# RS232.net
KiCad netlist of a schematic drawn in Altium Designer
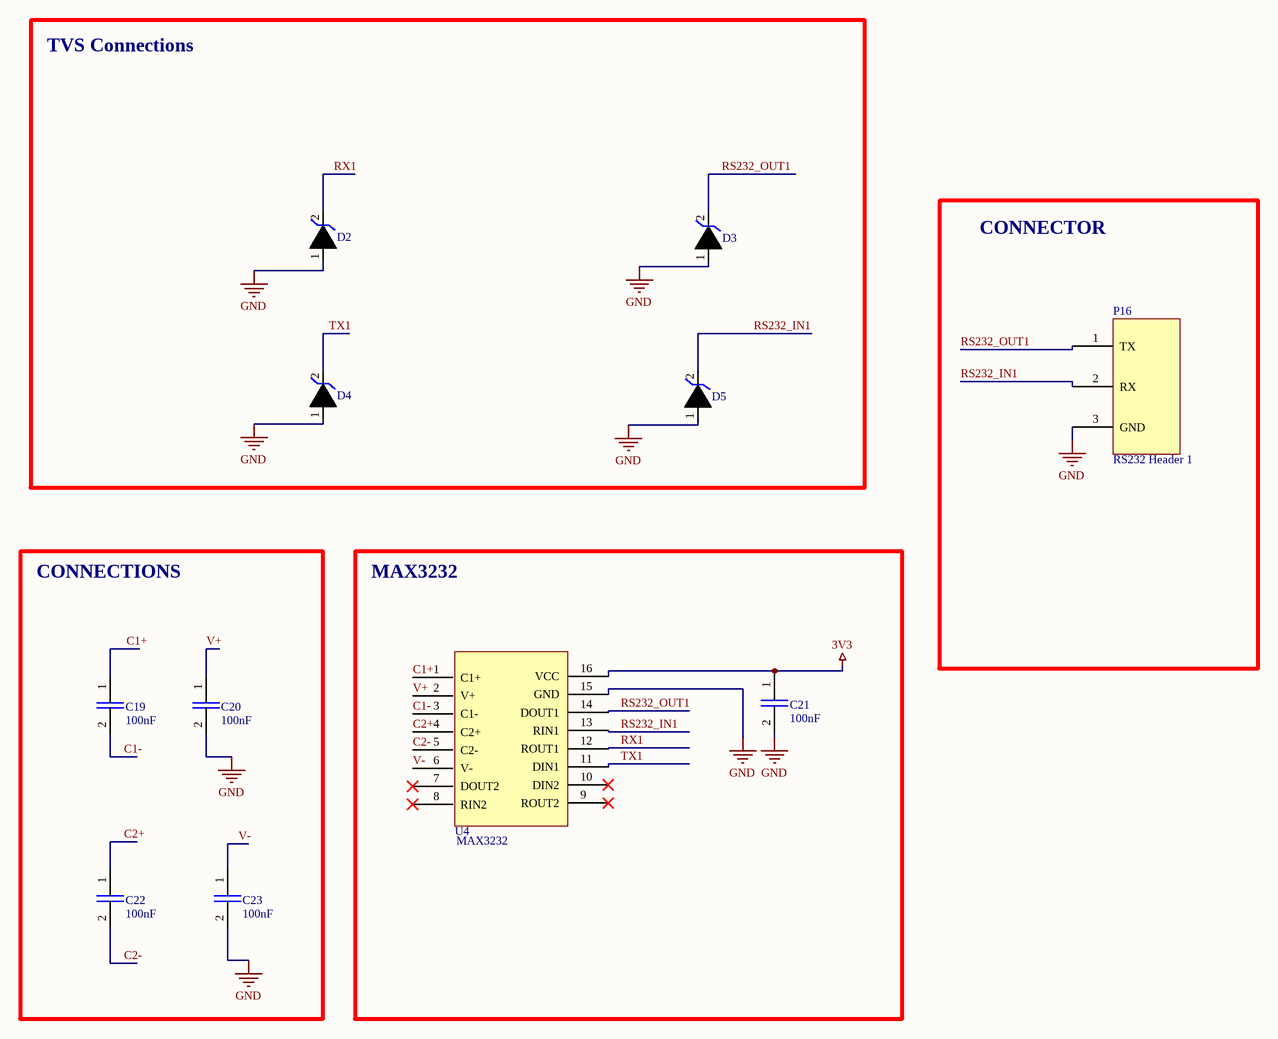
[diagram p0: RS232.SchDoc]

(export (version "E")
  (design (tool "Eeschema 10.0.6"))
  (components
    (comp (ref "C19")
      (value "100nF")
      (footprint "0603 Cap")
      (description "SMD 0603 (ceramic) capacitor")
      (fields
        (field (name "MANUFACTURER") "Murata")
        (field (name "MANUFACTURER PART NUMBER") "GRM21BR71C225KA12L")
      )
      (libsource (lib "Lib") (part "0603 Cap"))
    )
    (comp (ref "C20")
      (value "100nF")
      (footprint "0603 Cap")
      (description "SMD 0603 (ceramic) capacitor")
      (fields
        (field (name "MANUFACTURER") "Murata")
        (field (name "MANUFACTURER PART NUMBER") "GRM21BR71C225KA12L")
      )
      (libsource (lib "Lib") (part "0603 Cap"))
    )
    (comp (ref "C21")
      (value "100nF")
      (footprint "0603 Cap")
      (description "SMD 0603 (ceramic) capacitor")
      (fields
        (field (name "MANUFACTURER") "Murata")
        (field (name "MANUFACTURER PART NUMBER") "GRM21BR71C225KA12L")
      )
      (libsource (lib "Lib") (part "0603 Cap"))
    )
    (comp (ref "C22")
      (value "100nF")
      (footprint "0603 Cap")
      (description "SMD 0603 (ceramic) capacitor")
      (fields
        (field (name "MANUFACTURER") "Murata")
        (field (name "MANUFACTURER PART NUMBER") "GRM21BR71C225KA12L")
      )
      (libsource (lib "Lib") (part "0603 Cap"))
    )
    (comp (ref "C23")
      (value "100nF")
      (footprint "0603 Cap")
      (description "SMD 0603 (ceramic) capacitor")
      (fields
        (field (name "MANUFACTURER") "Murata")
        (field (name "MANUFACTURER PART NUMBER") "GRM21BR71C225KA12L")
      )
      (libsource (lib "Lib") (part "0603 Cap"))
    )
    (comp (ref "D2")
      (value "TVS")
      (footprint "0805 TVS DIODE")
      (description "Schematic for TVS diode")
      (libsource (lib "Lib") (part "TVS Diode"))
    )
    (comp (ref "D3")
      (value "TVS")
      (footprint "0805 TVS DIODE")
      (description "Schematic for TVS diode")
      (libsource (lib "Lib") (part "TVS Diode"))
    )
    (comp (ref "D4")
      (value "TVS")
      (footprint "0805 TVS DIODE")
      (description "Schematic for TVS diode")
      (libsource (lib "Lib") (part "TVS Diode"))
    )
    (comp (ref "D5")
      (value "TVS")
      (footprint "0805 TVS DIODE")
      (description "Schematic for TVS diode")
      (libsource (lib "Lib") (part "TVS Diode"))
    )
    (comp (ref "P16")
      (value "RS232 Header 1")
      (footprint "WR-TBL 322 3H")
      (description "322 Series 3 pin header")
      (libsource (lib "Lib") (part "322-3H"))
    )
    (comp (ref "U4")
      (value "MAX3232")
      (footprint "16-PIN SOIC")
      (description "16-Pin SOIC package IC schematic")
      (libsource (lib "Lib") (part "16-PIN SOIC"))
    )
  )
  (nets
    (net (code "1") (name "/C1+") (class "Default")
      (node (ref "C19") (pin "1") (pinfunction "11_1") (pintype "passive"))
      (node (ref "U4") (pin "1") (pinfunction "C1+_1") (pintype "passive"))
    )
    (net (code "2") (name "/C1-") (class "Default")
      (node (ref "C19") (pin "2") (pinfunction "12_2") (pintype "passive"))
      (node (ref "U4") (pin "3") (pinfunction "C1-_3") (pintype "passive"))
    )
    (net (code "3") (name "/C2+") (class "Default")
      (node (ref "C22") (pin "1") (pinfunction "11_1") (pintype "passive"))
      (node (ref "U4") (pin "4") (pinfunction "C2+_4") (pintype "passive"))
    )
    (net (code "4") (name "/C2-") (class "Default")
      (node (ref "C22") (pin "2") (pinfunction "12_2") (pintype "passive"))
      (node (ref "U4") (pin "5") (pinfunction "C2-_5") (pintype "passive"))
    )
    (net (code "5") (name "/RS232_IN1") (class "Default")
      (node (ref "D5") (pin "2") (pinfunction "2_2") (pintype "passive"))
      (node (ref "P16") (pin "2") (pinfunction "RX_2") (pintype "passive"))
      (node (ref "U4") (pin "13") (pinfunction "RIN1_13") (pintype "passive"))
    )
    (net (code "6") (name "/RS232_OUT1") (class "Default")
      (node (ref "D3") (pin "2") (pinfunction "2_2") (pintype "passive"))
      (node (ref "P16") (pin "1") (pinfunction "TX_1") (pintype "passive"))
      (node (ref "U4") (pin "14") (pinfunction "DOUT1_14") (pintype "passive"))
    )
    (net (code "7") (name "/RX1") (class "Default")
      (node (ref "D2") (pin "2") (pinfunction "2_2") (pintype "passive"))
      (node (ref "U4") (pin "12") (pinfunction "ROUT1_12") (pintype "passive"))
    )
    (net (code "8") (name "/TX1") (class "Default")
      (node (ref "D4") (pin "2") (pinfunction "2_2") (pintype "passive"))
      (node (ref "U4") (pin "11") (pinfunction "DIN1_11") (pintype "passive"))
    )
    (net (code "9") (name "/V+") (class "Default")
      (node (ref "C20") (pin "1") (pinfunction "11_1") (pintype "passive"))
      (node (ref "U4") (pin "2") (pinfunction "V+_2") (pintype "passive"))
    )
    (net (code "10") (name "/V-") (class "Default")
      (node (ref "C23") (pin "1") (pinfunction "11_1") (pintype "passive"))
      (node (ref "U4") (pin "6") (pinfunction "V-_6") (pintype "passive"))
    )
    (net (code "11") (name "3V3") (class "Default")
      (node (ref "C21") (pin "1") (pinfunction "11_1") (pintype "passive"))
      (node (ref "U4") (pin "16") (pinfunction "VCC_16") (pintype "passive"))
    )
    (net (code "12") (name "GND") (class "Default")
      (node (ref "C20") (pin "2") (pinfunction "12_2") (pintype "passive"))
      (node (ref "C21") (pin "2") (pinfunction "12_2") (pintype "passive"))
      (node (ref "C23") (pin "2") (pinfunction "12_2") (pintype "passive"))
      (node (ref "D2") (pin "1") (pinfunction "1_1") (pintype "passive"))
      (node (ref "D3") (pin "1") (pinfunction "1_1") (pintype "passive"))
      (node (ref "D4") (pin "1") (pinfunction "1_1") (pintype "passive"))
      (node (ref "D5") (pin "1") (pinfunction "1_1") (pintype "passive"))
      (node (ref "P16") (pin "3") (pinfunction "GND_3") (pintype "passive"))
      (node (ref "U4") (pin "15") (pinfunction "GND_15") (pintype "passive"))
    )
    (net (code "13") (name "unconnected-(U4-DIN2-Pad10)") (class "Default")
      (node (ref "U4") (pin "10") (pinfunction "DIN2_10") (pintype "passive+no_connect"))
    )
    (net (code "14") (name "unconnected-(U4-DOUT2-Pad7)") (class "Default")
      (node (ref "U4") (pin "7") (pinfunction "DOUT2_7") (pintype "passive+no_connect"))
    )
    (net (code "15") (name "unconnected-(U4-RIN2-Pad8)") (class "Default")
      (node (ref "U4") (pin "8") (pinfunction "RIN2_8") (pintype "passive+no_connect"))
    )
    (net (code "16") (name "unconnected-(U4-ROUT2-Pad9)") (class "Default")
      (node (ref "U4") (pin "9") (pinfunction "ROUT2_9") (pintype "passive+no_connect"))
    )
  )
)
